# batteryBalancer.net
KiCad netlist of a schematic drawn in EAGLE
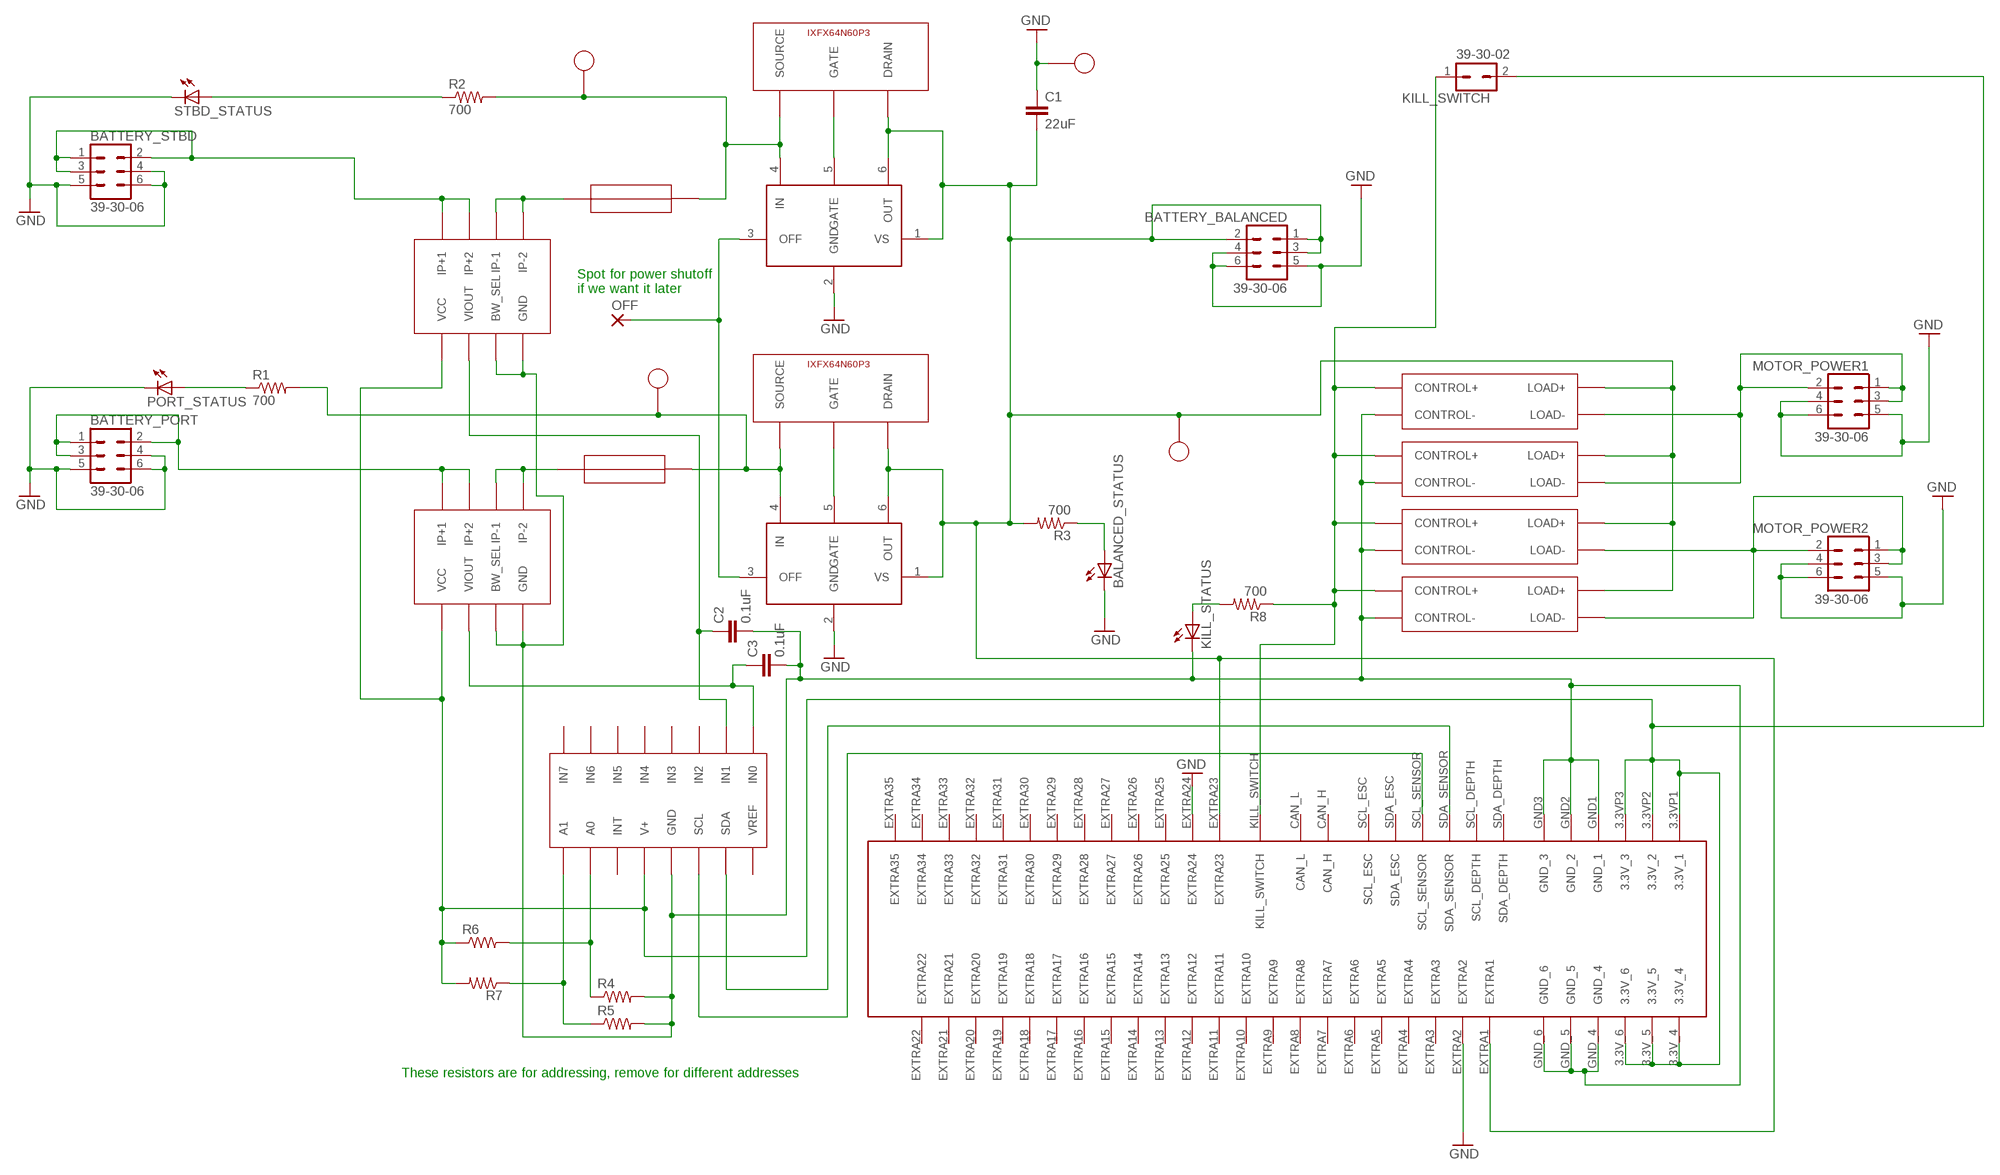
[diagram p0: schematic, sheet 1]

(export (version "E")
  (design (tool "Eeschema 10.0.6"))
  (components
    (comp (ref "ADC")
      (value "ADC128D818")
      (footprint "eagle-import:TSSOP-16")
      (libsource (lib "eagle-import") (part "ADC128D818"))
    )
    (comp (ref "BALANCED_STATUS")
      (value "LTST-S270GKT")
      (footprint "eagle-import:LTST-S270GKT")
      (libsource (lib "eagle-import") (part "LTST-S270GKT"))
    )
    (comp (ref "BATTERY_BALANCED")
      (value "39-30-06")
      (footprint "eagle-import:39-30-_06_")
      (libsource (lib "eagle-import") (part "39-30-?06?"))
    )
    (comp (ref "BATTERY_PORT")
      (value "39-30-06")
      (footprint "eagle-import:39-30-_06_")
      (libsource (lib "eagle-import") (part "39-30-?06?"))
    )
    (comp (ref "BATTERY_STBD")
      (value "39-30-06")
      (footprint "eagle-import:39-30-_06_")
      (libsource (lib "eagle-import") (part "39-30-?06?"))
    )
    (comp (ref "C1")
      (value "22uF")
      (footprint "eagle-import:CAP-PTH-SMALL-KIT")
      (libsource (lib "eagle-import") (part "0.1UF-KIT-EZ-50V-20%"))
    )
    (comp (ref "C2")
      (value "0.1uF")
      (footprint "eagle-import:CAP-PTH-SMALL-KIT")
      (libsource (lib "eagle-import") (part "0.1UF-KIT-EZ-50V-20%"))
    )
    (comp (ref "C3")
      (value "0.1uF")
      (footprint "eagle-import:CAP-PTH-SMALL-KIT")
      (libsource (lib "eagle-import") (part "0.1UF-KIT-EZ-50V-20%"))
    )
    (comp (ref "EDGE_CONNECTOR")
      (value "5530843")
      (footprint "eagle-import:5530843-6-BOARDFINGERS")
      (libsource (lib "eagle-import") (part "5530843"))
    )
    (comp (ref "KILL_STATUS")
      (value "LTST-S270GKT")
      (footprint "eagle-import:LTST-S270GKT")
      (libsource (lib "eagle-import") (part "LTST-S270GKT"))
    )
    (comp (ref "KILL_SWITCH")
      (value "39-30-02")
      (footprint "eagle-import:39-30-_02_")
      (libsource (lib "eagle-import") (part "39-30-?02?"))
    )
    (comp (ref "MOTOR_POWER1")
      (value "39-30-06")
      (footprint "eagle-import:39-30-_06_")
      (libsource (lib "eagle-import") (part "39-30-?06?"))
    )
    (comp (ref "MOTOR_POWER2")
      (value "39-30-06")
      (footprint "eagle-import:39-30-_06_")
      (libsource (lib "eagle-import") (part "39-30-?06?"))
    )
    (comp (ref "OFF")
      (value "2,54/1,1")
      (footprint "eagle-import:2,54_1,1")
      (libsource (lib "eagle-import") (part "2,54/1,1"))
    )
    (comp (ref "PORT_CS")
      (value "ACS722")
      (footprint "eagle-import:SOIC-8")
      (libsource (lib "eagle-import") (part "ACS722"))
    )
    (comp (ref "PORT_FC")
      (value "LM5050-1")
      (footprint "eagle-import:SOT23-6")
      (libsource (lib "eagle-import") (part "LM5050-1"))
    )
    (comp (ref "PORT_FET")
      (value "IXFX64N60P3")
      (footprint "eagle-import:IXFX64N60P3")
      (libsource (lib "eagle-import") (part "IXFX64N60P3"))
    )
    (comp (ref "PORT_FUSE")
      (value "01220083Z")
      (footprint "eagle-import:01220083Z")
      (libsource (lib "eagle-import") (part "01220083Z"))
    )
    (comp (ref "PORT_STATUS")
      (value "LTST-S270GKT")
      (footprint "eagle-import:LTST-S270GKT")
      (libsource (lib "eagle-import") (part "LTST-S270GKT"))
    )
    (comp (ref "R1")
      (value "700")
      (footprint "eagle-import:0207_7")
      (libsource (lib "eagle-import") (part "R-US_0207/7"))
    )
    (comp (ref "R2")
      (value "700")
      (footprint "eagle-import:0207_7")
      (libsource (lib "eagle-import") (part "R-US_0207/7"))
    )
    (comp (ref "R3")
      (value "700")
      (footprint "eagle-import:0207_7")
      (libsource (lib "eagle-import") (part "R-US_0207/7"))
    )
    (comp (ref "R4")
      (value "R-US_0204/5")
      (footprint "eagle-import:0204_5")
      (libsource (lib "eagle-import") (part "resistor_348_R-US_0204/5"))
    )
    (comp (ref "R5")
      (value "R-US_0204/5")
      (footprint "eagle-import:0204_5")
      (libsource (lib "eagle-import") (part "resistor_348_R-US_0204/5"))
    )
    (comp (ref "R6")
      (value "R-US_0204/5")
      (footprint "eagle-import:0204_5")
      (libsource (lib "eagle-import") (part "resistor_348_R-US_0204/5"))
    )
    (comp (ref "R7")
      (value "R-US_0204/5")
      (footprint "eagle-import:0204_5")
      (libsource (lib "eagle-import") (part "resistor_348_R-US_0204/5"))
    )
    (comp (ref "R8")
      (value "700")
      (footprint "eagle-import:0207_7")
      (libsource (lib "eagle-import") (part "R-US_0207/7"))
    )
    (comp (ref "RELAY2")
      (value "CMX60D20")
      (footprint "eagle-import:CMX60D20")
      (libsource (lib "eagle-import") (part "CMX60D20"))
    )
    (comp (ref "RELAY3")
      (value "CMX60D20")
      (footprint "eagle-import:CMX60D20")
      (libsource (lib "eagle-import") (part "CMX60D20"))
    )
    (comp (ref "RELAY4")
      (value "CMX60D20")
      (footprint "eagle-import:CMX60D20")
      (libsource (lib "eagle-import") (part "CMX60D20"))
    )
    (comp (ref "RLAY1")
      (value "CMX60D20")
      (footprint "eagle-import:CMX60D20")
      (libsource (lib "eagle-import") (part "CMX60D20"))
    )
    (comp (ref "STBD_CS")
      (value "ACS722")
      (footprint "eagle-import:SOIC-8")
      (libsource (lib "eagle-import") (part "ACS722"))
    )
    (comp (ref "STBD_FC")
      (value "LM5050-1")
      (footprint "eagle-import:SOT23-6")
      (libsource (lib "eagle-import") (part "LM5050-1"))
    )
    (comp (ref "STBD_FET")
      (value "IXFX64N60P3")
      (footprint "eagle-import:IXFX64N60P3")
      (libsource (lib "eagle-import") (part "IXFX64N60P3"))
    )
    (comp (ref "STBD_FUSE")
      (value "01220083Z")
      (footprint "eagle-import:01220083Z")
      (libsource (lib "eagle-import") (part "01220083Z"))
    )
    (comp (ref "STBD_STATUS")
      (value "LTST-S270GKT")
      (footprint "eagle-import:LTST-S270GKT")
      (libsource (lib "eagle-import") (part "LTST-S270GKT"))
    )
    (comp (ref "U$1")
      (value "5010_C")
      (footprint "eagle-import:5010_C")
      (libsource (lib "eagle-import") (part "5010_C"))
    )
    (comp (ref "U$2")
      (value "5010_C")
      (footprint "eagle-import:5010_C")
      (libsource (lib "eagle-import") (part "5010_C"))
    )
    (comp (ref "U$3")
      (value "5010_C")
      (footprint "eagle-import:5010_C")
      (libsource (lib "eagle-import") (part "5010_C"))
    )
    (comp (ref "U$4")
      (value "5010_C")
      (footprint "eagle-import:5010_C")
      (libsource (lib "eagle-import") (part "5010_C"))
    )
  )
  (nets
    (net (code "1") (name "GND") (class "Default")
      (node (ref "BALANCED_STATUS") (pin "CATHODE") (pinfunction "C_CATHODE") (pintype "passive"))
      (node (ref "BATTERY_BALANCED") (pin "4") (pinfunction "4_4") (pintype "passive"))
      (node (ref "BATTERY_BALANCED") (pin "5") (pinfunction "5_5") (pintype "passive"))
      (node (ref "BATTERY_BALANCED") (pin "6") (pinfunction "6_6") (pintype "passive"))
      (node (ref "BATTERY_PORT") (pin "4") (pinfunction "4_4") (pintype "passive"))
      (node (ref "BATTERY_PORT") (pin "5") (pinfunction "5_5") (pintype "passive"))
      (node (ref "BATTERY_PORT") (pin "6") (pinfunction "6_6") (pintype "passive"))
      (node (ref "BATTERY_STBD") (pin "4") (pinfunction "4_4") (pintype "passive"))
      (node (ref "BATTERY_STBD") (pin "5") (pinfunction "5_5") (pintype "passive"))
      (node (ref "BATTERY_STBD") (pin "6") (pinfunction "6_6") (pintype "passive"))
      (node (ref "C1") (pin "1") (pinfunction "1_1") (pintype "passive"))
      (node (ref "EDGE_CONNECTOR") (pin "EXTRA2") (pinfunction "EXTRA2_EXTRA2") (pintype "bidirectional"))
      (node (ref "EDGE_CONNECTOR") (pin "EXTRA24") (pinfunction "EXTRA24_EXTRA24") (pintype "bidirectional"))
      (node (ref "MOTOR_POWER1") (pin "4") (pinfunction "4_4") (pintype "passive"))
      (node (ref "MOTOR_POWER1") (pin "5") (pinfunction "5_5") (pintype "passive"))
      (node (ref "MOTOR_POWER1") (pin "6") (pinfunction "6_6") (pintype "passive"))
      (node (ref "MOTOR_POWER2") (pin "4") (pinfunction "4_4") (pintype "passive"))
      (node (ref "MOTOR_POWER2") (pin "5") (pinfunction "5_5") (pintype "passive"))
      (node (ref "MOTOR_POWER2") (pin "6") (pinfunction "6_6") (pintype "passive"))
      (node (ref "PORT_FC") (pin "2") (pinfunction "GND_2") (pintype "bidirectional"))
      (node (ref "PORT_STATUS") (pin "CATHODE") (pinfunction "C_CATHODE") (pintype "passive"))
      (node (ref "STBD_FC") (pin "2") (pinfunction "GND_2") (pintype "bidirectional"))
      (node (ref "STBD_STATUS") (pin "CATHODE") (pinfunction "C_CATHODE") (pintype "passive"))
      (node (ref "U$4") (pin "P$1") (pinfunction "P$1_P$1") (pintype "bidirectional"))
    )
    (net (code "2") (name "Net-(ADC-PadA0)") (class "Default")
      (node (ref "ADC") (pin "A0") (pinfunction "A0_A0") (pintype "bidirectional"))
      (node (ref "R4") (pin "1") (pinfunction "1_1") (pintype "passive"))
      (node (ref "R6") (pin "2") (pinfunction "2_2") (pintype "passive"))
    )
    (net (code "3") (name "Net-(ADC-PadA1)") (class "Default")
      (node (ref "ADC") (pin "A1") (pinfunction "A1_A1") (pintype "bidirectional"))
      (node (ref "R5") (pin "1") (pinfunction "1_1") (pintype "passive"))
      (node (ref "R7") (pin "1") (pinfunction "1_1") (pintype "passive"))
    )
    (net (code "4") (name "Net-(ADC-PadIN0)") (class "Default")
      (node (ref "ADC") (pin "IN0") (pinfunction "IN0_IN0") (pintype "bidirectional"))
      (node (ref "C3") (pin "1") (pinfunction "1_1") (pintype "passive"))
      (node (ref "PORT_CS") (pin "VIOUT") (pinfunction "VIOUT_VIOUT") (pintype "bidirectional"))
    )
    (net (code "5") (name "Net-(ADC-PadIN1)") (class "Default")
      (node (ref "ADC") (pin "IN1") (pinfunction "IN1_IN1") (pintype "bidirectional"))
      (node (ref "C2") (pin "1") (pinfunction "1_1") (pintype "passive"))
      (node (ref "STBD_CS") (pin "VIOUT") (pinfunction "VIOUT_VIOUT") (pintype "bidirectional"))
    )
    (net (code "6") (name "Net-(ADC-PadSCL)") (class "Default")
      (node (ref "ADC") (pin "SCL") (pinfunction "SCL_SCL") (pintype "bidirectional"))
      (node (ref "EDGE_CONNECTOR") (pin "SCL_SENSOR") (pinfunction "SCL_SENSOR_SCL_SENSOR") (pintype "bidirectional"))
    )
    (net (code "7") (name "Net-(ADC-PadSDA)") (class "Default")
      (node (ref "ADC") (pin "SDA") (pinfunction "SDA_SDA") (pintype "bidirectional"))
      (node (ref "EDGE_CONNECTOR") (pin "SDA_SENSOR") (pinfunction "SDA_SENSOR_SDA_SENSOR") (pintype "bidirectional"))
    )
    (net (code "8") (name "Net-(BALANCED_STATUS-A)") (class "Default")
      (node (ref "BALANCED_STATUS") (pin "ANODE") (pinfunction "A_ANODE") (pintype "passive"))
      (node (ref "R3") (pin "1") (pinfunction "1_1") (pintype "passive"))
    )
    (net (code "9") (name "Net-(BATTERY_PORT-Pad1)") (class "Default")
      (node (ref "BATTERY_PORT") (pin "1") (pinfunction "1_1") (pintype "passive"))
      (node (ref "BATTERY_PORT") (pin "2") (pinfunction "2_2") (pintype "passive"))
      (node (ref "BATTERY_PORT") (pin "3") (pinfunction "3_3") (pintype "passive"))
      (node (ref "PORT_CS") (pin "IP+1") (pinfunction "IP+1_IP+1") (pintype "bidirectional"))
      (node (ref "PORT_CS") (pin "IP+2") (pinfunction "IP+2_IP+2") (pintype "bidirectional"))
    )
    (net (code "10") (name "Net-(BATTERY_STBD-Pad1)") (class "Default")
      (node (ref "BATTERY_STBD") (pin "1") (pinfunction "1_1") (pintype "passive"))
      (node (ref "BATTERY_STBD") (pin "2") (pinfunction "2_2") (pintype "passive"))
      (node (ref "BATTERY_STBD") (pin "3") (pinfunction "3_3") (pintype "passive"))
      (node (ref "STBD_CS") (pin "IP+1") (pinfunction "IP+1_IP+1") (pintype "bidirectional"))
      (node (ref "STBD_CS") (pin "IP+2") (pinfunction "IP+2_IP+2") (pintype "bidirectional"))
    )
    (net (code "11") (name "Net-(EDGE_CONNECTOR-3.3V_1)") (class "Default")
      (node (ref "ADC") (pin "V+") (pinfunction "V+_V+") (pintype "bidirectional"))
      (node (ref "EDGE_CONNECTOR") (pin "3.3VP1") (pinfunction "3.3V_1_3.3VP1") (pintype "bidirectional"))
      (node (ref "EDGE_CONNECTOR") (pin "3.3VP2") (pinfunction "3.3V_2_3.3VP2") (pintype "bidirectional"))
      (node (ref "EDGE_CONNECTOR") (pin "3.3VP3") (pinfunction "3.3V_3_3.3VP3") (pintype "bidirectional"))
      (node (ref "EDGE_CONNECTOR") (pin "3.3V_4") (pinfunction "3.3V_4_3.3V_4") (pintype "bidirectional"))
      (node (ref "EDGE_CONNECTOR") (pin "3.3V_5") (pinfunction "3.3V_5_3.3V_5") (pintype "bidirectional"))
      (node (ref "EDGE_CONNECTOR") (pin "3.3V_6") (pinfunction "3.3V_6_3.3V_6") (pintype "bidirectional"))
      (node (ref "KILL_SWITCH") (pin "2") (pinfunction "2_2") (pintype "passive"))
      (node (ref "PORT_CS") (pin "VCC") (pinfunction "VCC_VCC") (pintype "bidirectional"))
      (node (ref "R6") (pin "1") (pinfunction "1_1") (pintype "passive"))
      (node (ref "R7") (pin "2") (pinfunction "2_2") (pintype "passive"))
      (node (ref "STBD_CS") (pin "VCC") (pinfunction "VCC_VCC") (pintype "bidirectional"))
    )
    (net (code "12") (name "Net-(EDGE_CONNECTOR-GND_1)") (class "Default")
      (node (ref "ADC") (pin "GND") (pinfunction "GND_GND") (pintype "bidirectional"))
      (node (ref "C2") (pin "2") (pinfunction "2_2") (pintype "passive"))
      (node (ref "C3") (pin "2") (pinfunction "2_2") (pintype "passive"))
      (node (ref "EDGE_CONNECTOR") (pin "GND1") (pinfunction "GND_1_GND1") (pintype "bidirectional"))
      (node (ref "EDGE_CONNECTOR") (pin "GND2") (pinfunction "GND_2_GND2") (pintype "bidirectional"))
      (node (ref "EDGE_CONNECTOR") (pin "GND3") (pinfunction "GND_3_GND3") (pintype "bidirectional"))
      (node (ref "EDGE_CONNECTOR") (pin "GND_4") (pinfunction "GND_4_GND_4") (pintype "bidirectional"))
      (node (ref "EDGE_CONNECTOR") (pin "GND_5") (pinfunction "GND_5_GND_5") (pintype "bidirectional"))
      (node (ref "EDGE_CONNECTOR") (pin "GND_6") (pinfunction "GND_6_GND_6") (pintype "bidirectional"))
      (node (ref "KILL_STATUS") (pin "CATHODE") (pinfunction "C_CATHODE") (pintype "passive"))
      (node (ref "PORT_CS") (pin "BW_SEL") (pinfunction "BW_SEL_BW_SEL") (pintype "bidirectional"))
      (node (ref "PORT_CS") (pin "GND") (pinfunction "GND_GND") (pintype "bidirectional"))
      (node (ref "R4") (pin "2") (pinfunction "2_2") (pintype "passive"))
      (node (ref "R5") (pin "2") (pinfunction "2_2") (pintype "passive"))
      (node (ref "RELAY2") (pin "CONTROL-") (pinfunction "CONTROL-_CONTROL-") (pintype "bidirectional"))
      (node (ref "RELAY3") (pin "CONTROL-") (pinfunction "CONTROL-_CONTROL-") (pintype "bidirectional"))
      (node (ref "RELAY4") (pin "CONTROL-") (pinfunction "CONTROL-_CONTROL-") (pintype "bidirectional"))
      (node (ref "RLAY1") (pin "CONTROL-") (pinfunction "CONTROL-_CONTROL-") (pintype "bidirectional"))
      (node (ref "STBD_CS") (pin "BW_SEL") (pinfunction "BW_SEL_BW_SEL") (pintype "bidirectional"))
      (node (ref "STBD_CS") (pin "GND") (pinfunction "GND_GND") (pintype "bidirectional"))
    )
    (net (code "13") (name "Net-(EDGE_CONNECTOR-PadKILL_SWITCH)") (class "Default")
      (node (ref "EDGE_CONNECTOR") (pin "KILL_SWITCH") (pinfunction "KILL_SWITCH_KILL_SWITCH") (pintype "bidirectional"))
      (node (ref "KILL_SWITCH") (pin "1") (pinfunction "1_1") (pintype "passive"))
      (node (ref "R8") (pin "1") (pinfunction "1_1") (pintype "passive"))
      (node (ref "RELAY2") (pin "CONTROL+") (pinfunction "CONTROL+_CONTROL+") (pintype "bidirectional"))
      (node (ref "RELAY3") (pin "CONTROL+") (pinfunction "CONTROL+_CONTROL+") (pintype "bidirectional"))
      (node (ref "RELAY4") (pin "CONTROL+") (pinfunction "CONTROL+_CONTROL+") (pintype "bidirectional"))
      (node (ref "RLAY1") (pin "CONTROL+") (pinfunction "CONTROL+_CONTROL+") (pintype "bidirectional"))
    )
    (net (code "14") (name "Net-(KILL_STATUS-A)") (class "Default")
      (node (ref "KILL_STATUS") (pin "ANODE") (pinfunction "A_ANODE") (pintype "passive"))
      (node (ref "R8") (pin "2") (pinfunction "2_2") (pintype "passive"))
    )
    (net (code "15") (name "Net-(MOTOR_POWER1-Pad1)") (class "Default")
      (node (ref "MOTOR_POWER1") (pin "1") (pinfunction "1_1") (pintype "passive"))
      (node (ref "MOTOR_POWER1") (pin "2") (pinfunction "2_2") (pintype "passive"))
      (node (ref "MOTOR_POWER1") (pin "3") (pinfunction "3_3") (pintype "passive"))
      (node (ref "RELAY2") (pin "LOAD-") (pinfunction "LOAD-_LOAD-") (pintype "bidirectional"))
      (node (ref "RLAY1") (pin "LOAD-") (pinfunction "LOAD-_LOAD-") (pintype "bidirectional"))
    )
    (net (code "16") (name "Net-(MOTOR_POWER2-Pad1)") (class "Default")
      (node (ref "MOTOR_POWER2") (pin "1") (pinfunction "1_1") (pintype "passive"))
      (node (ref "MOTOR_POWER2") (pin "2") (pinfunction "2_2") (pintype "passive"))
      (node (ref "MOTOR_POWER2") (pin "3") (pinfunction "3_3") (pintype "passive"))
      (node (ref "RELAY3") (pin "LOAD-") (pinfunction "LOAD-_LOAD-") (pintype "bidirectional"))
      (node (ref "RELAY4") (pin "LOAD-") (pinfunction "LOAD-_LOAD-") (pintype "bidirectional"))
    )
    (net (code "17") (name "Net-(OFF-P)") (class "Default")
      (node (ref "OFF") (pin "1") (pinfunction "P_1") (pintype "passive"))
      (node (ref "PORT_FC") (pin "3") (pinfunction "OFF_3") (pintype "bidirectional"))
      (node (ref "STBD_FC") (pin "3") (pinfunction "OFF_3") (pintype "bidirectional"))
    )
    (net (code "18") (name "Net-(PORT_CS-PadIP-1)") (class "Default")
      (node (ref "PORT_CS") (pin "IP-1") (pinfunction "IP-1_IP-1") (pintype "bidirectional"))
      (node (ref "PORT_CS") (pin "IP-2") (pinfunction "IP-2_IP-2") (pintype "bidirectional"))
      (node (ref "PORT_FUSE") (pin "P$1") (pinfunction "P$1_P$1") (pintype "bidirectional"))
      (node (ref "PORT_FUSE") (pin "P$2") (pinfunction "P$1_P$2") (pintype "bidirectional"))
    )
    (net (code "19") (name "Net-(PORT_FC-GATE)") (class "Default")
      (node (ref "PORT_FC") (pin "5") (pinfunction "GATE_5") (pintype "bidirectional"))
      (node (ref "PORT_FET") (pin "GATE") (pinfunction "GATE_GATE") (pintype "bidirectional"))
    )
    (net (code "20") (name "Net-(PORT_FC-IN)") (class "Default")
      (node (ref "PORT_FC") (pin "4") (pinfunction "IN_4") (pintype "bidirectional"))
      (node (ref "PORT_FET") (pin "SOURCE") (pinfunction "SOURCE_SOURCE") (pintype "bidirectional"))
      (node (ref "PORT_FUSE") (pin "P$3") (pinfunction "P$2_P$3") (pintype "bidirectional"))
      (node (ref "PORT_FUSE") (pin "P$4") (pinfunction "P$2_P$4") (pintype "bidirectional"))
      (node (ref "R1") (pin "2") (pinfunction "2_2") (pintype "passive"))
      (node (ref "U$2") (pin "P$1") (pinfunction "P$1_P$1") (pintype "bidirectional"))
    )
    (net (code "21") (name "Net-(PORT_FC-OUT)") (class "Default")
      (node (ref "BATTERY_BALANCED") (pin "1") (pinfunction "1_1") (pintype "passive"))
      (node (ref "BATTERY_BALANCED") (pin "2") (pinfunction "2_2") (pintype "passive"))
      (node (ref "BATTERY_BALANCED") (pin "3") (pinfunction "3_3") (pintype "passive"))
      (node (ref "C1") (pin "2") (pinfunction "2_2") (pintype "passive"))
      (node (ref "EDGE_CONNECTOR") (pin "EXTRA1") (pinfunction "EXTRA1_EXTRA1") (pintype "bidirectional"))
      (node (ref "EDGE_CONNECTOR") (pin "EXTRA23") (pinfunction "EXTRA23_EXTRA23") (pintype "bidirectional"))
      (node (ref "PORT_FC") (pin "1") (pinfunction "VS_1") (pintype "bidirectional"))
      (node (ref "PORT_FC") (pin "6") (pinfunction "OUT_6") (pintype "bidirectional"))
      (node (ref "PORT_FET") (pin "DRAIN") (pinfunction "DRAIN_DRAIN") (pintype "bidirectional"))
      (node (ref "R3") (pin "2") (pinfunction "2_2") (pintype "passive"))
      (node (ref "RELAY2") (pin "LOAD+") (pinfunction "LOAD+_LOAD+") (pintype "bidirectional"))
      (node (ref "RELAY3") (pin "LOAD+") (pinfunction "LOAD+_LOAD+") (pintype "bidirectional"))
      (node (ref "RELAY4") (pin "LOAD+") (pinfunction "LOAD+_LOAD+") (pintype "bidirectional"))
      (node (ref "RLAY1") (pin "LOAD+") (pinfunction "LOAD+_LOAD+") (pintype "bidirectional"))
      (node (ref "STBD_FC") (pin "1") (pinfunction "VS_1") (pintype "bidirectional"))
      (node (ref "STBD_FC") (pin "6") (pinfunction "OUT_6") (pintype "bidirectional"))
      (node (ref "STBD_FET") (pin "DRAIN") (pinfunction "DRAIN_DRAIN") (pintype "bidirectional"))
      (node (ref "U$3") (pin "P$1") (pinfunction "P$1_P$1") (pintype "bidirectional"))
    )
    (net (code "22") (name "Net-(PORT_STATUS-A)") (class "Default")
      (node (ref "PORT_STATUS") (pin "ANODE") (pinfunction "A_ANODE") (pintype "passive"))
      (node (ref "R1") (pin "1") (pinfunction "1_1") (pintype "passive"))
    )
    (net (code "23") (name "Net-(STBD_CS-PadIP-1)") (class "Default")
      (node (ref "STBD_CS") (pin "IP-1") (pinfunction "IP-1_IP-1") (pintype "bidirectional"))
      (node (ref "STBD_CS") (pin "IP-2") (pinfunction "IP-2_IP-2") (pintype "bidirectional"))
      (node (ref "STBD_FUSE") (pin "P$1") (pinfunction "P$1_P$1") (pintype "bidirectional"))
      (node (ref "STBD_FUSE") (pin "P$2") (pinfunction "P$1_P$2") (pintype "bidirectional"))
    )
    (net (code "24") (name "Net-(STBD_FC-GATE)") (class "Default")
      (node (ref "STBD_FC") (pin "5") (pinfunction "GATE_5") (pintype "bidirectional"))
      (node (ref "STBD_FET") (pin "GATE") (pinfunction "GATE_GATE") (pintype "bidirectional"))
    )
    (net (code "25") (name "Net-(STBD_FC-IN)") (class "Default")
      (node (ref "R2") (pin "2") (pinfunction "2_2") (pintype "passive"))
      (node (ref "STBD_FC") (pin "4") (pinfunction "IN_4") (pintype "bidirectional"))
      (node (ref "STBD_FET") (pin "SOURCE") (pinfunction "SOURCE_SOURCE") (pintype "bidirectional"))
      (node (ref "STBD_FUSE") (pin "P$3") (pinfunction "P$2_P$3") (pintype "bidirectional"))
      (node (ref "STBD_FUSE") (pin "P$4") (pinfunction "P$2_P$4") (pintype "bidirectional"))
      (node (ref "U$1") (pin "P$1") (pinfunction "P$1_P$1") (pintype "bidirectional"))
    )
    (net (code "26") (name "Net-(STBD_STATUS-A)") (class "Default")
      (node (ref "R2") (pin "1") (pinfunction "1_1") (pintype "passive"))
      (node (ref "STBD_STATUS") (pin "ANODE") (pinfunction "A_ANODE") (pintype "passive"))
    )
    (net (code "27") (name "unconnected-(ADC-PadIN2)") (class "Default")
      (node (ref "ADC") (pin "IN2") (pinfunction "IN2_IN2") (pintype "bidirectional"))
    )
    (net (code "28") (name "unconnected-(ADC-PadIN3)") (class "Default")
      (node (ref "ADC") (pin "IN3") (pinfunction "IN3_IN3") (pintype "bidirectional"))
    )
    (net (code "29") (name "unconnected-(ADC-PadIN4)") (class "Default")
      (node (ref "ADC") (pin "IN4") (pinfunction "IN4_IN4") (pintype "bidirectional"))
    )
    (net (code "30") (name "unconnected-(ADC-PadIN5)") (class "Default")
      (node (ref "ADC") (pin "IN5") (pinfunction "IN5_IN5") (pintype "bidirectional"))
    )
    (net (code "31") (name "unconnected-(ADC-PadIN6)") (class "Default")
      (node (ref "ADC") (pin "IN6") (pinfunction "IN6_IN6") (pintype "bidirectional"))
    )
    (net (code "32") (name "unconnected-(ADC-PadIN7)") (class "Default")
      (node (ref "ADC") (pin "IN7") (pinfunction "IN7_IN7") (pintype "bidirectional"))
    )
    (net (code "33") (name "unconnected-(ADC-PadINT)") (class "Default")
      (node (ref "ADC") (pin "INT") (pinfunction "INT_INT") (pintype "bidirectional"))
    )
    (net (code "34") (name "unconnected-(ADC-PadVREF)") (class "Default")
      (node (ref "ADC") (pin "VREF") (pinfunction "VREF_VREF") (pintype "bidirectional"))
    )
    (net (code "35") (name "unconnected-(EDGE_CONNECTOR-PadCAN_H)") (class "Default")
      (node (ref "EDGE_CONNECTOR") (pin "CAN_H") (pinfunction "CAN_H_CAN_H") (pintype "bidirectional"))
    )
    (net (code "36") (name "unconnected-(EDGE_CONNECTOR-PadCAN_L)") (class "Default")
      (node (ref "EDGE_CONNECTOR") (pin "CAN_L") (pinfunction "CAN_L_CAN_L") (pintype "bidirectional"))
    )
    (net (code "37") (name "unconnected-(EDGE_CONNECTOR-PadEXTRA3)") (class "Default")
      (node (ref "EDGE_CONNECTOR") (pin "EXTRA3") (pinfunction "EXTRA3_EXTRA3") (pintype "bidirectional"))
    )
    (net (code "38") (name "unconnected-(EDGE_CONNECTOR-PadEXTRA4)") (class "Default")
      (node (ref "EDGE_CONNECTOR") (pin "EXTRA4") (pinfunction "EXTRA4_EXTRA4") (pintype "bidirectional"))
    )
    (net (code "39") (name "unconnected-(EDGE_CONNECTOR-PadEXTRA5)") (class "Default")
      (node (ref "EDGE_CONNECTOR") (pin "EXTRA5") (pinfunction "EXTRA5_EXTRA5") (pintype "bidirectional"))
    )
    (net (code "40") (name "unconnected-(EDGE_CONNECTOR-PadEXTRA6)") (class "Default")
      (node (ref "EDGE_CONNECTOR") (pin "EXTRA6") (pinfunction "EXTRA6_EXTRA6") (pintype "bidirectional"))
    )
    (net (code "41") (name "unconnected-(EDGE_CONNECTOR-PadEXTRA7)") (class "Default")
      (node (ref "EDGE_CONNECTOR") (pin "EXTRA7") (pinfunction "EXTRA7_EXTRA7") (pintype "bidirectional"))
    )
    (net (code "42") (name "unconnected-(EDGE_CONNECTOR-PadEXTRA8)") (class "Default")
      (node (ref "EDGE_CONNECTOR") (pin "EXTRA8") (pinfunction "EXTRA8_EXTRA8") (pintype "bidirectional"))
    )
    (net (code "43") (name "unconnected-(EDGE_CONNECTOR-PadEXTRA9)") (class "Default")
      (node (ref "EDGE_CONNECTOR") (pin "EXTRA9") (pinfunction "EXTRA9_EXTRA9") (pintype "bidirectional"))
    )
    (net (code "44") (name "unconnected-(EDGE_CONNECTOR-PadEXTRA10)") (class "Default")
      (node (ref "EDGE_CONNECTOR") (pin "EXTRA10") (pinfunction "EXTRA10_EXTRA10") (pintype "bidirectional"))
    )
    (net (code "45") (name "unconnected-(EDGE_CONNECTOR-PadEXTRA11)") (class "Default")
      (node (ref "EDGE_CONNECTOR") (pin "EXTRA11") (pinfunction "EXTRA11_EXTRA11") (pintype "bidirectional"))
    )
    (net (code "46") (name "unconnected-(EDGE_CONNECTOR-PadEXTRA12)") (class "Default")
      (node (ref "EDGE_CONNECTOR") (pin "EXTRA12") (pinfunction "EXTRA12_EXTRA12") (pintype "bidirectional"))
    )
    (net (code "47") (name "unconnected-(EDGE_CONNECTOR-PadEXTRA13)") (class "Default")
      (node (ref "EDGE_CONNECTOR") (pin "EXTRA13") (pinfunction "EXTRA13_EXTRA13") (pintype "bidirectional"))
    )
    (net (code "48") (name "unconnected-(EDGE_CONNECTOR-PadEXTRA14)") (class "Default")
      (node (ref "EDGE_CONNECTOR") (pin "EXTRA14") (pinfunction "EXTRA14_EXTRA14") (pintype "bidirectional"))
    )
    (net (code "49") (name "unconnected-(EDGE_CONNECTOR-PadEXTRA15)") (class "Default")
      (node (ref "EDGE_CONNECTOR") (pin "EXTRA15") (pinfunction "EXTRA15_EXTRA15") (pintype "bidirectional"))
    )
    (net (code "50") (name "unconnected-(EDGE_CONNECTOR-PadEXTRA16)") (class "Default")
      (node (ref "EDGE_CONNECTOR") (pin "EXTRA16") (pinfunction "EXTRA16_EXTRA16") (pintype "bidirectional"))
    )
    (net (code "51") (name "unconnected-(EDGE_CONNECTOR-PadEXTRA17)") (class "Default")
      (node (ref "EDGE_CONNECTOR") (pin "EXTRA17") (pinfunction "EXTRA17_EXTRA17") (pintype "bidirectional"))
    )
    (net (code "52") (name "unconnected-(EDGE_CONNECTOR-PadEXTRA18)") (class "Default")
      (node (ref "EDGE_CONNECTOR") (pin "EXTRA18") (pinfunction "EXTRA18_EXTRA18") (pintype "bidirectional"))
    )
    (net (code "53") (name "unconnected-(EDGE_CONNECTOR-PadEXTRA19)") (class "Default")
      (node (ref "EDGE_CONNECTOR") (pin "EXTRA19") (pinfunction "EXTRA19_EXTRA19") (pintype "bidirectional"))
    )
    (net (code "54") (name "unconnected-(EDGE_CONNECTOR-PadEXTRA20)") (class "Default")
      (node (ref "EDGE_CONNECTOR") (pin "EXTRA20") (pinfunction "EXTRA20_EXTRA20") (pintype "bidirectional"))
    )
    (net (code "55") (name "unconnected-(EDGE_CONNECTOR-PadEXTRA21)") (class "Default")
      (node (ref "EDGE_CONNECTOR") (pin "EXTRA21") (pinfunction "EXTRA21_EXTRA21") (pintype "bidirectional"))
    )
    (net (code "56") (name "unconnected-(EDGE_CONNECTOR-PadEXTRA22)") (class "Default")
      (node (ref "EDGE_CONNECTOR") (pin "EXTRA22") (pinfunction "EXTRA22_EXTRA22") (pintype "bidirectional"))
    )
    (net (code "57") (name "unconnected-(EDGE_CONNECTOR-PadEXTRA25)") (class "Default")
      (node (ref "EDGE_CONNECTOR") (pin "EXTRA25") (pinfunction "EXTRA25_EXTRA25") (pintype "bidirectional"))
    )
    (net (code "58") (name "unconnected-(EDGE_CONNECTOR-PadEXTRA26)") (class "Default")
      (node (ref "EDGE_CONNECTOR") (pin "EXTRA26") (pinfunction "EXTRA26_EXTRA26") (pintype "bidirectional"))
    )
    (net (code "59") (name "unconnected-(EDGE_CONNECTOR-PadEXTRA27)") (class "Default")
      (node (ref "EDGE_CONNECTOR") (pin "EXTRA27") (pinfunction "EXTRA27_EXTRA27") (pintype "bidirectional"))
    )
    (net (code "60") (name "unconnected-(EDGE_CONNECTOR-PadEXTRA28)") (class "Default")
      (node (ref "EDGE_CONNECTOR") (pin "EXTRA28") (pinfunction "EXTRA28_EXTRA28") (pintype "bidirectional"))
    )
    (net (code "61") (name "unconnected-(EDGE_CONNECTOR-PadEXTRA29)") (class "Default")
      (node (ref "EDGE_CONNECTOR") (pin "EXTRA29") (pinfunction "EXTRA29_EXTRA29") (pintype "bidirectional"))
    )
    (net (code "62") (name "unconnected-(EDGE_CONNECTOR-PadEXTRA30)") (class "Default")
      (node (ref "EDGE_CONNECTOR") (pin "EXTRA30") (pinfunction "EXTRA30_EXTRA30") (pintype "bidirectional"))
    )
    (net (code "63") (name "unconnected-(EDGE_CONNECTOR-PadEXTRA31)") (class "Default")
      (node (ref "EDGE_CONNECTOR") (pin "EXTRA31") (pinfunction "EXTRA31_EXTRA31") (pintype "bidirectional"))
    )
    (net (code "64") (name "unconnected-(EDGE_CONNECTOR-PadEXTRA32)") (class "Default")
      (node (ref "EDGE_CONNECTOR") (pin "EXTRA32") (pinfunction "EXTRA32_EXTRA32") (pintype "bidirectional"))
    )
    (net (code "65") (name "unconnected-(EDGE_CONNECTOR-PadEXTRA33)") (class "Default")
      (node (ref "EDGE_CONNECTOR") (pin "EXTRA33") (pinfunction "EXTRA33_EXTRA33") (pintype "bidirectional"))
    )
    (net (code "66") (name "unconnected-(EDGE_CONNECTOR-PadEXTRA34)") (class "Default")
      (node (ref "EDGE_CONNECTOR") (pin "EXTRA34") (pinfunction "EXTRA34_EXTRA34") (pintype "bidirectional"))
    )
    (net (code "67") (name "unconnected-(EDGE_CONNECTOR-PadEXTRA35)") (class "Default")
      (node (ref "EDGE_CONNECTOR") (pin "EXTRA35") (pinfunction "EXTRA35_EXTRA35") (pintype "bidirectional"))
    )
    (net (code "68") (name "unconnected-(EDGE_CONNECTOR-PadSCL_DEPTH)") (class "Default")
      (node (ref "EDGE_CONNECTOR") (pin "SCL_DEPTH") (pinfunction "SCL_DEPTH_SCL_DEPTH") (pintype "bidirectional"))
    )
    (net (code "69") (name "unconnected-(EDGE_CONNECTOR-PadSCL_ESC)") (class "Default")
      (node (ref "EDGE_CONNECTOR") (pin "SCL_ESC") (pinfunction "SCL_ESC_SCL_ESC") (pintype "bidirectional"))
    )
    (net (code "70") (name "unconnected-(EDGE_CONNECTOR-PadSDA_DEPTH)") (class "Default")
      (node (ref "EDGE_CONNECTOR") (pin "SDA_DEPTH") (pinfunction "SDA_DEPTH_SDA_DEPTH") (pintype "bidirectional"))
    )
    (net (code "71") (name "unconnected-(EDGE_CONNECTOR-PadSDA_ESC)") (class "Default")
      (node (ref "EDGE_CONNECTOR") (pin "SDA_ESC") (pinfunction "SDA_ESC_SDA_ESC") (pintype "bidirectional"))
    )
  )
)
